# PRE_1_0.net
KiCad netlist of a schematic drawn in EAGLE
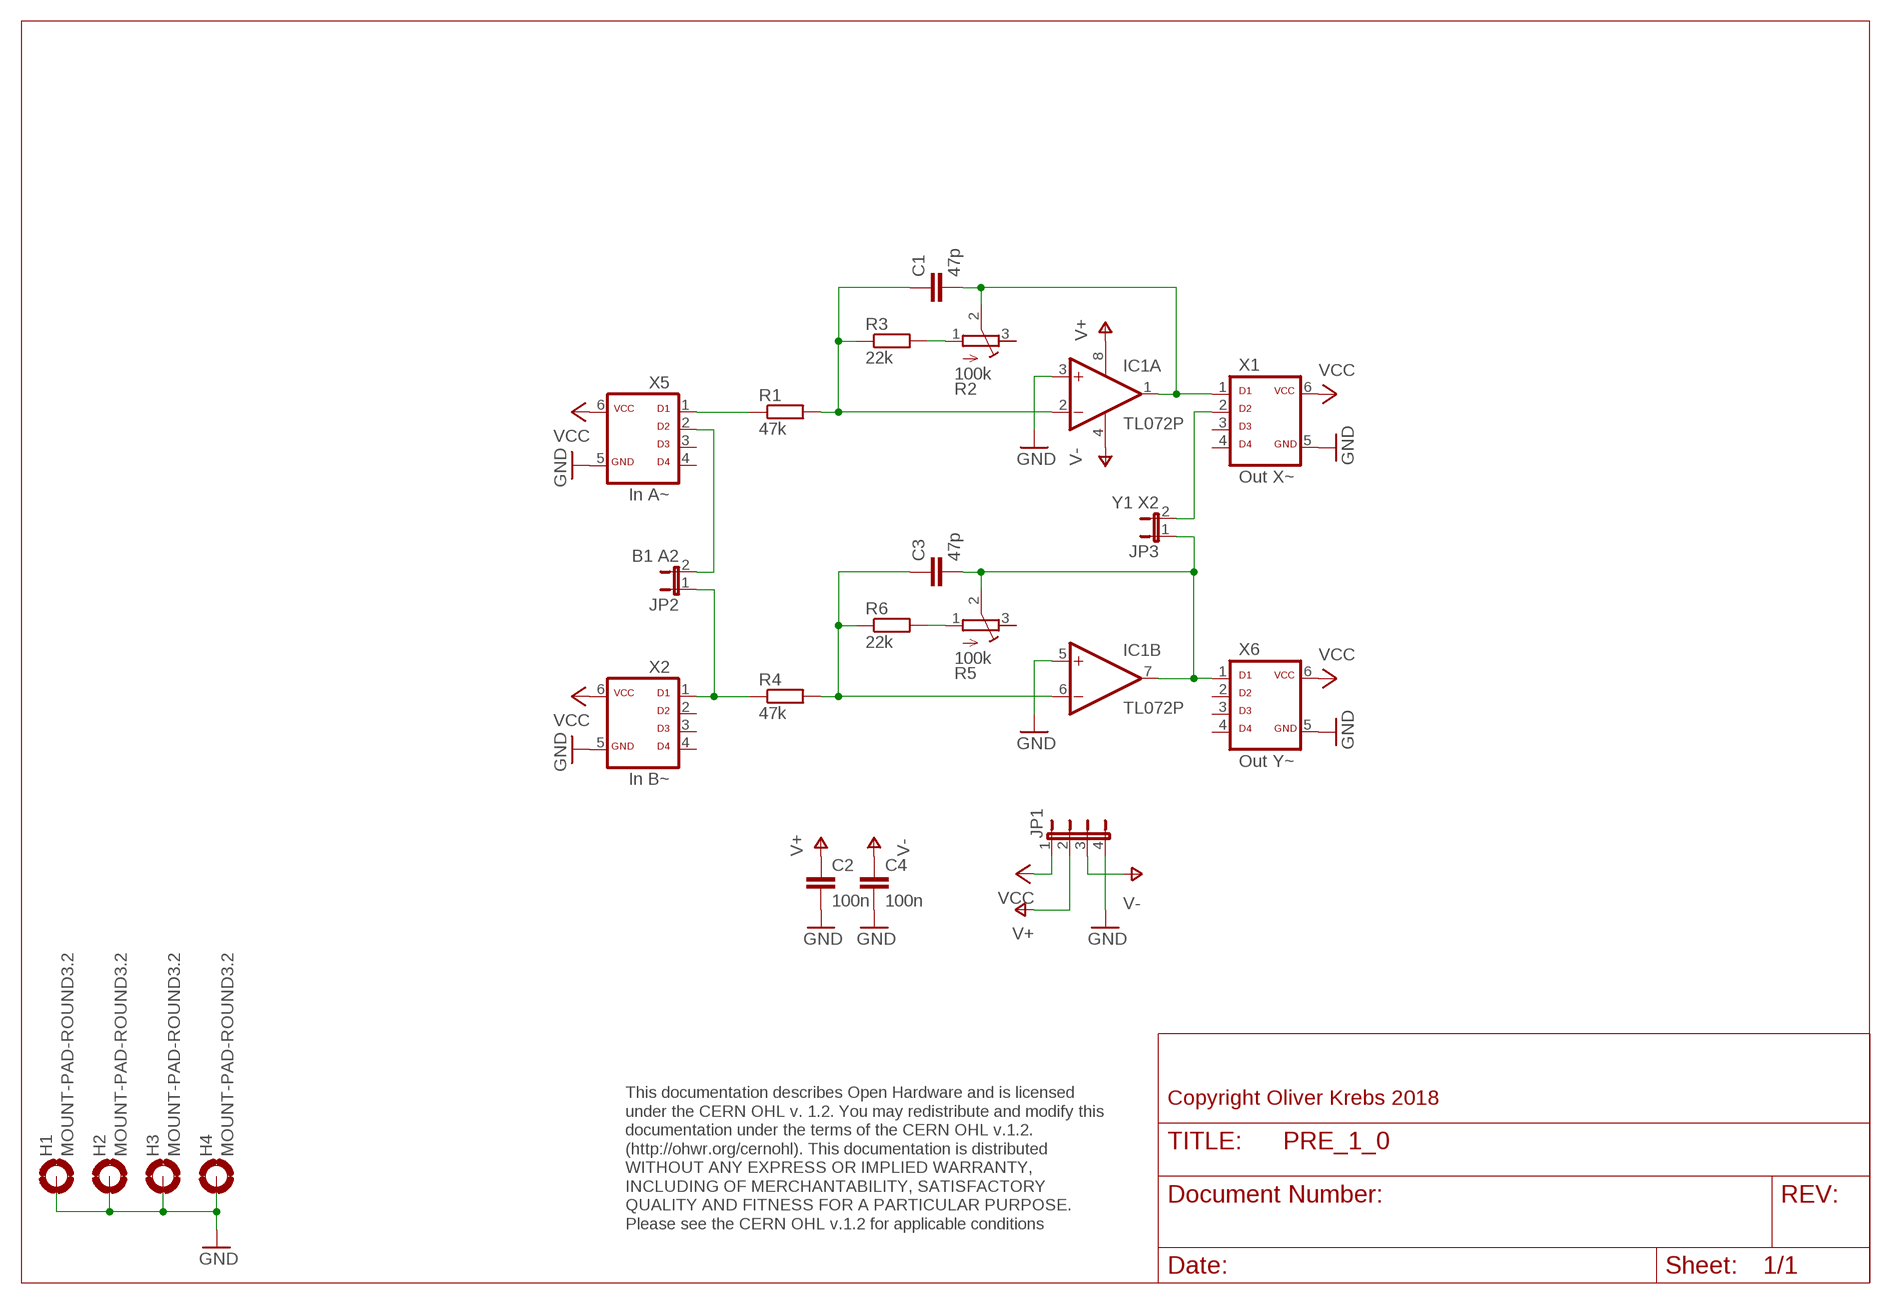
[diagram p0: schematic, sheet 1]

(export (version "E")
  (design (tool "Eeschema 10.0.6"))
  (components
    (comp (ref "C1")
      (value "47p")
      (footprint "eagle-import:C050-025X075")
      (libsource (lib "eagle-import") (part "C-EU050-025X075"))
    )
    (comp (ref "C2")
      (value "100n")
      (footprint "eagle-import:C050-025X075")
      (libsource (lib "eagle-import") (part "C-EU050-025X075"))
    )
    (comp (ref "C3")
      (value "47p")
      (footprint "eagle-import:C050-025X075")
      (libsource (lib "eagle-import") (part "C-EU050-025X075"))
    )
    (comp (ref "C4")
      (value "100n")
      (footprint "eagle-import:C050-025X075")
      (libsource (lib "eagle-import") (part "C-EU050-025X075"))
    )
    (comp (ref "H1")
      (value "MOUNT-PAD-ROUND3.2")
      (footprint "eagle-import:3,2-PAD")
      (libsource (lib "eagle-import") (part "MOUNT-PAD-ROUND3.2"))
    )
    (comp (ref "H2")
      (value "MOUNT-PAD-ROUND3.2")
      (footprint "eagle-import:3,2-PAD")
      (libsource (lib "eagle-import") (part "MOUNT-PAD-ROUND3.2"))
    )
    (comp (ref "H3")
      (value "MOUNT-PAD-ROUND3.2")
      (footprint "eagle-import:3,2-PAD")
      (libsource (lib "eagle-import") (part "MOUNT-PAD-ROUND3.2"))
    )
    (comp (ref "H4")
      (value "MOUNT-PAD-ROUND3.2")
      (footprint "eagle-import:3,2-PAD")
      (libsource (lib "eagle-import") (part "MOUNT-PAD-ROUND3.2"))
    )
    (comp (ref "IC1")
      (value "TL072P")
      (footprint "eagle-import:DIL08")
      (libsource (lib "eagle-import") (part "TL072P"))
    )
    (comp (ref "JP1")
      (value "JP4E")
      (footprint "eagle-import:JP4")
      (libsource (lib "eagle-import") (part "JP4E"))
    )
    (comp (ref "JP2")
      (value "B1 A2")
      (footprint "eagle-import:JP1")
      (libsource (lib "eagle-import") (part "JP1E"))
    )
    (comp (ref "JP3")
      (value "Y1 X2")
      (footprint "eagle-import:JP1")
      (libsource (lib "eagle-import") (part "JP1E"))
    )
    (comp (ref "R1")
      (value "47k")
      (footprint "eagle-import:0207_10")
      (libsource (lib "eagle-import") (part "R-EU_0207/10"))
    )
    (comp (ref "R2")
      (value "100k")
      (footprint "eagle-import:ACP-6L")
      (libsource (lib "eagle-import") (part "R-TRIMMACP"))
    )
    (comp (ref "R3")
      (value "22k")
      (footprint "eagle-import:0207_10")
      (libsource (lib "eagle-import") (part "R-EU_0207/10"))
    )
    (comp (ref "R4")
      (value "47k")
      (footprint "eagle-import:0207_10")
      (libsource (lib "eagle-import") (part "R-EU_0207/10"))
    )
    (comp (ref "R5")
      (value "100k")
      (footprint "eagle-import:ACP-6L")
      (libsource (lib "eagle-import") (part "R-TRIMMACP"))
    )
    (comp (ref "R6")
      (value "22k")
      (footprint "eagle-import:0207_10")
      (libsource (lib "eagle-import") (part "R-EU_0207/10"))
    )
    (comp (ref "X1")
      (value "Out X~")
      (footprint "eagle-import:ML-6")
      (libsource (lib "eagle-import") (part "ML6D"))
    )
    (comp (ref "X2")
      (value "In B~")
      (footprint "eagle-import:ML-6")
      (libsource (lib "eagle-import") (part "ML6D"))
    )
    (comp (ref "X5")
      (value "In A~")
      (footprint "eagle-import:ML-6")
      (libsource (lib "eagle-import") (part "ML6D"))
    )
    (comp (ref "X6")
      (value "Out Y~")
      (footprint "eagle-import:ML-6")
      (libsource (lib "eagle-import") (part "ML6D"))
    )
  )
  (nets
    (net (code "1") (name "GND") (class "Default")
      (node (ref "C2") (pin "2") (pinfunction "2_2") (pintype "passive"))
      (node (ref "C4") (pin "2") (pinfunction "2_2") (pintype "passive"))
      (node (ref "H1") (pin "B3,2") (pinfunction "MOUNT_B3,2") (pintype "passive"))
      (node (ref "H2") (pin "B3,2") (pinfunction "MOUNT_B3,2") (pintype "passive"))
      (node (ref "H3") (pin "B3,2") (pinfunction "MOUNT_B3,2") (pintype "passive"))
      (node (ref "H4") (pin "B3,2") (pinfunction "MOUNT_B3,2") (pintype "passive"))
      (node (ref "IC1") (pin "3") (pinfunction "+IN_3") (pintype "input"))
      (node (ref "IC1") (pin "5") (pinfunction "+IN_5") (pintype "input"))
      (node (ref "JP1") (pin "4") (pinfunction "4_4") (pintype "passive"))
      (node (ref "X1") (pin "5") (pinfunction "5_5") (pintype "passive"))
      (node (ref "X2") (pin "5") (pinfunction "5_5") (pintype "passive"))
      (node (ref "X5") (pin "5") (pinfunction "5_5") (pintype "passive"))
      (node (ref "X6") (pin "5") (pinfunction "5_5") (pintype "passive"))
    )
    (net (code "2") (name "Net-(IC1A--IN)") (class "Default")
      (node (ref "C1") (pin "1") (pinfunction "1_1") (pintype "passive"))
      (node (ref "IC1") (pin "2") (pinfunction "-IN_2") (pintype "input"))
      (node (ref "R1") (pin "2") (pinfunction "2_2") (pintype "passive"))
      (node (ref "R3") (pin "1") (pinfunction "1_1") (pintype "passive"))
    )
    (net (code "3") (name "Net-(IC1A-OUT)") (class "Default")
      (node (ref "C1") (pin "2") (pinfunction "2_2") (pintype "passive"))
      (node (ref "IC1") (pin "1") (pinfunction "OUT_1") (pintype "output"))
      (node (ref "R2") (pin "2") (pinfunction "S_2") (pintype "passive"))
      (node (ref "X1") (pin "1") (pinfunction "1_1") (pintype "passive"))
    )
    (net (code "4") (name "Net-(IC1B--IN)") (class "Default")
      (node (ref "C3") (pin "1") (pinfunction "1_1") (pintype "passive"))
      (node (ref "IC1") (pin "6") (pinfunction "-IN_6") (pintype "input"))
      (node (ref "R4") (pin "2") (pinfunction "2_2") (pintype "passive"))
      (node (ref "R6") (pin "1") (pinfunction "1_1") (pintype "passive"))
    )
    (net (code "5") (name "Net-(IC1B-OUT)") (class "Default")
      (node (ref "C3") (pin "2") (pinfunction "2_2") (pintype "passive"))
      (node (ref "IC1") (pin "7") (pinfunction "OUT_7") (pintype "output"))
      (node (ref "JP3") (pin "1") (pinfunction "1_1") (pintype "passive"))
      (node (ref "R5") (pin "2") (pinfunction "S_2") (pintype "passive"))
      (node (ref "X6") (pin "1") (pinfunction "1_1") (pintype "passive"))
    )
    (net (code "6") (name "Net-(JP2-Pad1)") (class "Default")
      (node (ref "JP2") (pin "1") (pinfunction "1_1") (pintype "passive"))
      (node (ref "R4") (pin "1") (pinfunction "1_1") (pintype "passive"))
      (node (ref "X2") (pin "1") (pinfunction "1_1") (pintype "passive"))
    )
    (net (code "7") (name "Net-(JP2-Pad2)") (class "Default")
      (node (ref "JP2") (pin "2") (pinfunction "2_2") (pintype "passive"))
      (node (ref "X5") (pin "2") (pinfunction "2_2") (pintype "passive"))
    )
    (net (code "8") (name "Net-(JP3-Pad2)") (class "Default")
      (node (ref "JP3") (pin "2") (pinfunction "2_2") (pintype "passive"))
      (node (ref "X1") (pin "2") (pinfunction "2_2") (pintype "passive"))
    )
    (net (code "9") (name "Net-(R1-Pad1)") (class "Default")
      (node (ref "R1") (pin "1") (pinfunction "1_1") (pintype "passive"))
      (node (ref "X5") (pin "1") (pinfunction "1_1") (pintype "passive"))
    )
    (net (code "10") (name "Net-(R2-A)") (class "Default")
      (node (ref "R2") (pin "1") (pinfunction "A_1") (pintype "passive"))
      (node (ref "R3") (pin "2") (pinfunction "2_2") (pintype "passive"))
    )
    (net (code "11") (name "Net-(R5-A)") (class "Default")
      (node (ref "R5") (pin "1") (pinfunction "A_1") (pintype "passive"))
      (node (ref "R6") (pin "2") (pinfunction "2_2") (pintype "passive"))
    )
    (net (code "12") (name "V+") (class "Default")
      (node (ref "C2") (pin "1") (pinfunction "1_1") (pintype "passive"))
      (node (ref "IC1") (pin "8") (pinfunction "V+_8") (pintype "power_in"))
      (node (ref "JP1") (pin "2") (pinfunction "2_2") (pintype "passive"))
    )
    (net (code "13") (name "V-") (class "Default")
      (node (ref "C4") (pin "1") (pinfunction "1_1") (pintype "passive"))
      (node (ref "IC1") (pin "4") (pinfunction "V-_4") (pintype "power_in"))
      (node (ref "JP1") (pin "3") (pinfunction "3_3") (pintype "passive"))
    )
    (net (code "14") (name "VCC") (class "Default")
      (node (ref "JP1") (pin "1") (pinfunction "1_1") (pintype "passive"))
      (node (ref "X1") (pin "6") (pinfunction "6_6") (pintype "passive"))
      (node (ref "X2") (pin "6") (pinfunction "6_6") (pintype "passive"))
      (node (ref "X5") (pin "6") (pinfunction "6_6") (pintype "passive"))
      (node (ref "X6") (pin "6") (pinfunction "6_6") (pintype "passive"))
    )
    (net (code "15") (name "unconnected-(R2-E-Pad3)") (class "Default")
      (node (ref "R2") (pin "3") (pinfunction "E_3") (pintype "passive"))
    )
    (net (code "16") (name "unconnected-(R5-E-Pad3)") (class "Default")
      (node (ref "R5") (pin "3") (pinfunction "E_3") (pintype "passive"))
    )
    (net (code "17") (name "unconnected-(X1-Pad3)") (class "Default")
      (node (ref "X1") (pin "3") (pinfunction "3_3") (pintype "passive"))
    )
    (net (code "18") (name "unconnected-(X1-Pad4)") (class "Default")
      (node (ref "X1") (pin "4") (pinfunction "4_4") (pintype "passive"))
    )
    (net (code "19") (name "unconnected-(X2-Pad2)") (class "Default")
      (node (ref "X2") (pin "2") (pinfunction "2_2") (pintype "passive"))
    )
    (net (code "20") (name "unconnected-(X2-Pad3)") (class "Default")
      (node (ref "X2") (pin "3") (pinfunction "3_3") (pintype "passive"))
    )
    (net (code "21") (name "unconnected-(X2-Pad4)") (class "Default")
      (node (ref "X2") (pin "4") (pinfunction "4_4") (pintype "passive"))
    )
    (net (code "22") (name "unconnected-(X5-Pad3)") (class "Default")
      (node (ref "X5") (pin "3") (pinfunction "3_3") (pintype "passive"))
    )
    (net (code "23") (name "unconnected-(X5-Pad4)") (class "Default")
      (node (ref "X5") (pin "4") (pinfunction "4_4") (pintype "passive"))
    )
    (net (code "24") (name "unconnected-(X6-Pad2)") (class "Default")
      (node (ref "X6") (pin "2") (pinfunction "2_2") (pintype "passive"))
    )
    (net (code "25") (name "unconnected-(X6-Pad3)") (class "Default")
      (node (ref "X6") (pin "3") (pinfunction "3_3") (pintype "passive"))
    )
    (net (code "26") (name "unconnected-(X6-Pad4)") (class "Default")
      (node (ref "X6") (pin "4") (pinfunction "4_4") (pintype "passive"))
    )
  )
)
